# camera.net
KiCad netlist of a schematic drawn in Altium Designer
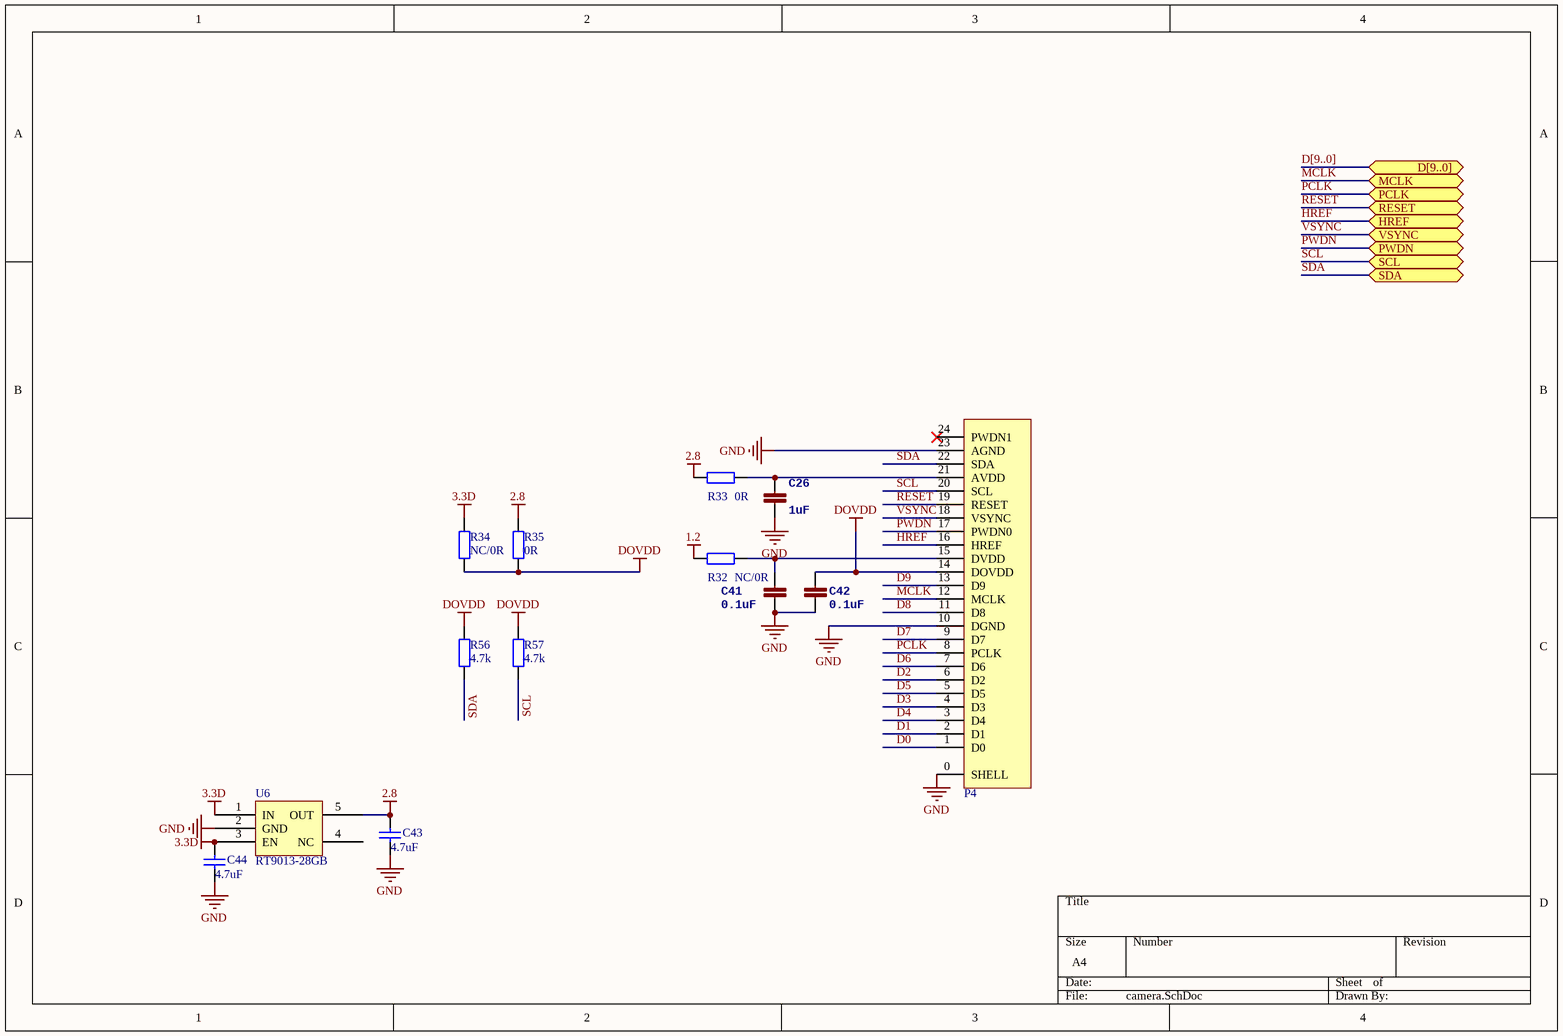
[diagram p0: camera.SchDoc]

(export (version "E")
  (design (tool "Eeschema 10.0.6"))
  (components
    (comp (ref "C26")
      (value "1uF")
      (footprint "0402")
      (description "<b>Capacitor</b>\nStandard 0603 ceramic capacitor, and 0.1\" leaded capacitor.")
      (fields (field (name "PARTNO") "CC0402ZRY5V7BB104"))
      (libsource (lib "pixhawk2") (part "CAP0402-CAP"))
    )
    (comp (ref "C41")
      (value "0.1uF")
      (footprint "0402")
      (description "<b>Capacitor</b>\nStandard 0603 ceramic capacitor, and 0.1\" leaded capacitor.")
      (fields (field (name "PARTNO") "CC0402ZRY5V7BB104"))
      (libsource (lib "pixhawk2") (part "CAP0402-CAP"))
    )
    (comp (ref "C42")
      (value "0.1uF")
      (footprint "0402")
      (description "<b>Capacitor</b>\nStandard 0603 ceramic capacitor, and 0.1\" leaded capacitor.")
      (fields (field (name "PARTNO") "CC0402ZRY5V7BB104"))
      (libsource (lib "pixhawk2") (part "CAP0402-CAP"))
    )
    (comp (ref "C43")
      (value "4.7uF")
      (footprint "0603")
      (description "Capacitor")
      (fields (field (name "PUBLISHER") "Altium Limited"))
      (libsource (lib "RTC6705") (part "Cap"))
    )
    (comp (ref "C44")
      (value "4.7uF")
      (footprint "0603")
      (description "Capacitor")
      (fields (field (name "PUBLISHER") "Altium Limited"))
      (libsource (lib "RTC6705") (part "Cap"))
    )
    (comp (ref "P4")
      (value "Camera24P-2")
      (footprint "FPC-0.5mm-24")
      (libsource (lib "sch") (part "Camera24P-2"))
    )
    (comp (ref "R32")
      (value "NC/0R")
      (footprint "0402")
      (description "Resistor")
      (fields (field (name "PUBLISHER") "Altium Limited"))
      (libsource (lib "") (part "Res2_1"))
    )
    (comp (ref "R33")
      (value "0R")
      (footprint "0402")
      (description "Resistor")
      (fields (field (name "PUBLISHER") "Altium Limited"))
      (libsource (lib "") (part "Res2_1"))
    )
    (comp (ref "R34")
      (value "NC/0R")
      (footprint "0402")
      (description "Resistor")
      (fields (field (name "PUBLISHER") "Altium Limited"))
      (libsource (lib "Miscellaneous Devices") (part "Res2"))
    )
    (comp (ref "R35")
      (value "0R")
      (footprint "0402")
      (description "Resistor")
      (fields (field (name "PUBLISHER") "Altium Limited"))
      (libsource (lib "Miscellaneous Devices") (part "Res2"))
    )
    (comp (ref "R56")
      (value "4.7k")
      (footprint "0402")
      (description "Resistor")
      (fields (field (name "PUBLISHER") "Altium Limited"))
      (libsource (lib "Miscellaneous Devices") (part "Res2"))
    )
    (comp (ref "R57")
      (value "4.7k")
      (footprint "0402")
      (description "Resistor")
      (fields (field (name "PUBLISHER") "Altium Limited"))
      (libsource (lib "Miscellaneous Devices") (part "Res2"))
    )
    (comp (ref "U6") (value "RT9013-28GB") (footprint "SOT23-5") (libsource (lib "RTC6705") (part "LP5907")))
  )
  (nets
    (net (code "1") (name "/D0") (class "Default")
      (node (ref "P4") (pin "1") (pinfunction "D0_1") (pintype "passive"))
    )
    (net (code "2") (name "/D1") (class "Default")
      (node (ref "P4") (pin "2") (pinfunction "D1_2") (pintype "passive"))
    )
    (net (code "3") (name "/D2") (class "Default")
      (node (ref "P4") (pin "6") (pinfunction "D2_6") (pintype "passive"))
    )
    (net (code "4") (name "/D3") (class "Default")
      (node (ref "P4") (pin "4") (pinfunction "D3_4") (pintype "passive"))
    )
    (net (code "5") (name "/D4") (class "Default")
      (node (ref "P4") (pin "3") (pinfunction "D4_3") (pintype "passive"))
    )
    (net (code "6") (name "/D5") (class "Default")
      (node (ref "P4") (pin "5") (pinfunction "D5_5") (pintype "passive"))
    )
    (net (code "7") (name "/D6") (class "Default")
      (node (ref "P4") (pin "7") (pinfunction "D6_7") (pintype "passive"))
    )
    (net (code "8") (name "/D7") (class "Default")
      (node (ref "P4") (pin "9") (pinfunction "D7_9") (pintype "passive"))
    )
    (net (code "9") (name "/D8") (class "Default")
      (node (ref "P4") (pin "11") (pinfunction "D8_11") (pintype "passive"))
    )
    (net (code "10") (name "/D9") (class "Default")
      (node (ref "P4") (pin "13") (pinfunction "D9_13") (pintype "passive"))
    )
    (net (code "12") (name "/HREF") (class "Default")
      (node (ref "P4") (pin "16") (pinfunction "HREF_16") (pintype "passive"))
    )
    (net (code "13") (name "/MCLK") (class "Default")
      (node (ref "P4") (pin "12") (pinfunction "MCLK_12") (pintype "passive"))
    )
    (net (code "14") (name "/PCLK") (class "Default")
      (node (ref "P4") (pin "8") (pinfunction "PCLK_8") (pintype "passive"))
    )
    (net (code "15") (name "/PWDN") (class "Default")
      (node (ref "P4") (pin "17") (pinfunction "PWDN0_17") (pintype "passive"))
    )
    (net (code "16") (name "/RESET") (class "Default")
      (node (ref "P4") (pin "19") (pinfunction "RESET_19") (pintype "passive"))
    )
    (net (code "17") (name "/SCL") (class "Default")
      (node (ref "P4") (pin "20") (pinfunction "SCL_20") (pintype "passive"))
      (node (ref "R57") (pin "2") (pinfunction "2_2") (pintype "passive"))
    )
    (net (code "18") (name "/SDA") (class "Default")
      (node (ref "P4") (pin "22") (pinfunction "SDA_22") (pintype "passive"))
      (node (ref "R56") (pin "2") (pinfunction "2_2") (pintype "passive"))
    )
    (net (code "19") (name "/VSYNC") (class "Default")
      (node (ref "P4") (pin "18") (pinfunction "VSYNC_18") (pintype "passive"))
    )
    (net (code "20") (name "1.2") (class "Default")
      (node (ref "R32") (pin "2") (pinfunction "2_2") (pintype "passive"))
    )
    (net (code "21") (name "2.8") (class "Default")
      (node (ref "C43") (pin "2") (pinfunction "2_2") (pintype "passive"))
      (node (ref "R33") (pin "2") (pinfunction "2_2") (pintype "passive"))
      (node (ref "R35") (pin "1") (pinfunction "1_1") (pintype "passive"))
      (node (ref "U6") (pin "5") (pinfunction "OUT_5") (pintype "passive"))
    )
    (net (code "22") (name "3.3D") (class "Default")
      (node (ref "C44") (pin "2") (pinfunction "2_2") (pintype "passive"))
      (node (ref "R34") (pin "1") (pinfunction "1_1") (pintype "passive"))
      (node (ref "U6") (pin "1") (pinfunction "IN_1") (pintype "passive"))
      (node (ref "U6") (pin "3") (pinfunction "EN_3") (pintype "passive"))
    )
    (net (code "23") (name "DOVDD") (class "Default")
      (node (ref "C42") (pin "2") (pinfunction "2_2") (pintype "passive"))
      (node (ref "P4") (pin "14") (pinfunction "DOVDD_14") (pintype "passive"))
      (node (ref "R34") (pin "2") (pinfunction "2_2") (pintype "passive"))
      (node (ref "R35") (pin "2") (pinfunction "2_2") (pintype "passive"))
      (node (ref "R56") (pin "1") (pinfunction "1_1") (pintype "passive"))
      (node (ref "R57") (pin "1") (pinfunction "1_1") (pintype "passive"))
    )
    (net (code "24") (name "GND") (class "Default")
      (node (ref "C26") (pin "1") (pinfunction "1_1") (pintype "passive"))
      (node (ref "C41") (pin "1") (pinfunction "1_1") (pintype "passive"))
      (node (ref "C42") (pin "1") (pinfunction "1_1") (pintype "passive"))
      (node (ref "C43") (pin "1") (pinfunction "1_1") (pintype "passive"))
      (node (ref "C44") (pin "1") (pinfunction "1_1") (pintype "passive"))
      (node (ref "P4") (pin "0") (pinfunction "SHELL_0") (pintype "passive"))
      (node (ref "P4") (pin "10") (pinfunction "DGND_10") (pintype "passive"))
      (node (ref "P4") (pin "23") (pinfunction "AGND_23") (pintype "passive"))
      (node (ref "U6") (pin "2") (pinfunction "GND_2") (pintype "passive"))
    )
    (net (code "25") (name "Net-(P4-AVDD)") (class "Default")
      (node (ref "C26") (pin "2") (pinfunction "2_2") (pintype "passive"))
      (node (ref "P4") (pin "21") (pinfunction "AVDD_21") (pintype "passive"))
      (node (ref "R33") (pin "1") (pinfunction "1_1") (pintype "passive"))
    )
    (net (code "26") (name "Net-(P4-DVDD)") (class "Default")
      (node (ref "C41") (pin "2") (pinfunction "2_2") (pintype "passive"))
      (node (ref "P4") (pin "15") (pinfunction "DVDD_15") (pintype "passive"))
      (node (ref "R32") (pin "1") (pinfunction "1_1") (pintype "passive"))
    )
    (net (code "27") (name "unconnected-(P4-PWDN1-Pad24)") (class "Default")
      (node (ref "P4") (pin "24") (pinfunction "PWDN1_24") (pintype "passive+no_connect"))
    )
    (net (code "28") (name "unconnected-(U6-NC-Pad4)") (class "Default")
      (node (ref "U6") (pin "4") (pinfunction "NC_4") (pintype "passive"))
    )
  )
)
